# femtoduinoUSB.net
KiCad netlist of a schematic drawn in EAGLE
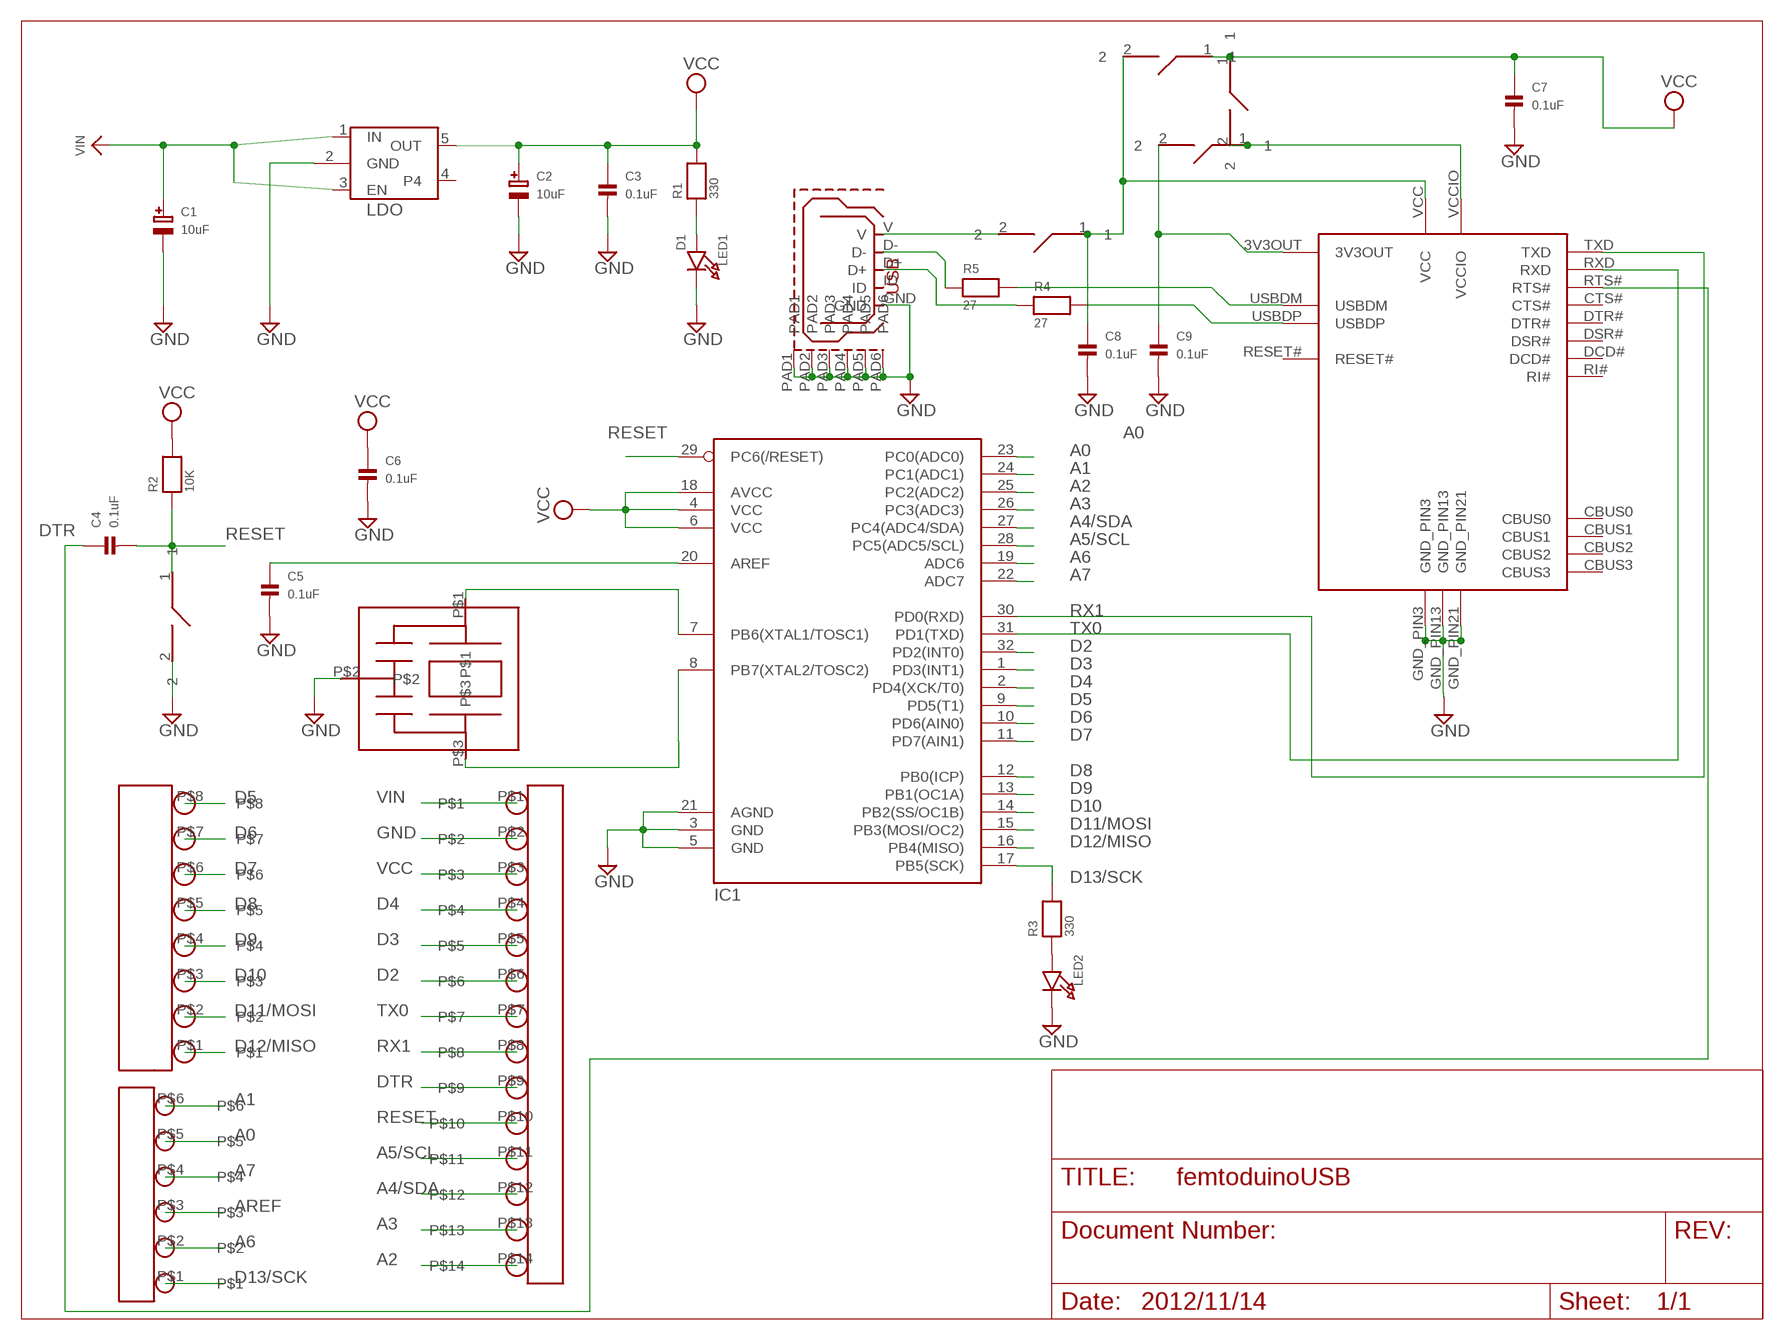
[diagram p0: schematic, sheet 1]

(export (version "E")
  (design (tool "Eeschema 10.0.6"))
  (components
    (comp (ref "C1")
      (value "10uF")
      (footprint "eagle-import:EIA3528-21_B-W")
      (libsource (lib "eagle-import") (part "CAP_TANTALUMB/3528_WAVE"))
    )
    (comp (ref "C2")
      (value "10uF")
      (footprint "eagle-import:EIA3528-21_B-W")
      (libsource (lib "eagle-import") (part "CAP_TANTALUMB/3528_WAVE"))
    )
    (comp (ref "C3")
      (value "0.1uF")
      (footprint "eagle-import:0402")
      (libsource (lib "eagle-import") (part "CAP_CERAMIC0402"))
    )
    (comp (ref "C4")
      (value "0.1uF")
      (footprint "eagle-import:0402")
      (libsource (lib "eagle-import") (part "CAP_CERAMIC0402"))
    )
    (comp (ref "C5")
      (value "0.1uF")
      (footprint "eagle-import:0402")
      (libsource (lib "eagle-import") (part "CAP_CERAMIC0402"))
    )
    (comp (ref "C6")
      (value "0.1uF")
      (footprint "eagle-import:0402")
      (libsource (lib "eagle-import") (part "CAP_CERAMIC0402"))
    )
    (comp (ref "C7")
      (value "0.1uF")
      (footprint "eagle-import:0402")
      (libsource (lib "eagle-import") (part "CAP_CERAMIC0402"))
    )
    (comp (ref "C8")
      (value "0.1uF")
      (footprint "eagle-import:0402")
      (libsource (lib "eagle-import") (part "CAP_CERAMIC0402"))
    )
    (comp (ref "C9")
      (value "0.1uF")
      (footprint "eagle-import:0402")
      (libsource (lib "eagle-import") (part "CAP_CERAMIC0402"))
    )
    (comp (ref "IC1")
      (value "ATMEGA168MLF")
      (footprint "eagle-import:MLF32")
      (libsource (lib "eagle-import") (part "ATMEGA168MLF"))
    )
    (comp (ref "IC2")
      (value "FT231XQ-R")
      (footprint "eagle-import:FTDI_FT231XQ-R_PACKAGE")
      (libsource (lib "eagle-import") (part "FT231XQ-R"))
    )
    (comp (ref "LED1")
      (value "D1")
      (footprint "eagle-import:CHIPLED_0805")
      (libsource (lib "eagle-import") (part "LED0805"))
    )
    (comp (ref "LED2")
      (value "LED0805")
      (footprint "eagle-import:CHIPLED_0805")
      (libsource (lib "eagle-import") (part "LED0805"))
    )
    (comp (ref "R1")
      (value "330")
      (footprint "eagle-import:0402")
      (libsource (lib "eagle-import") (part "RESISTOR0402"))
    )
    (comp (ref "R2")
      (value "10K")
      (footprint "eagle-import:0402")
      (libsource (lib "eagle-import") (part "RESISTOR0402"))
    )
    (comp (ref "R3")
      (value "330")
      (footprint "eagle-import:0402")
      (libsource (lib "eagle-import") (part "RESISTOR0402"))
    )
    (comp (ref "R4")
      (value "27")
      (footprint "eagle-import:0402")
      (libsource (lib "eagle-import") (part "RESISTOR0402"))
    )
    (comp (ref "R5")
      (value "27")
      (footprint "eagle-import:0402")
      (libsource (lib "eagle-import") (part "RESISTOR0402"))
    )
    (comp (ref "SJ1")
      (value "SPST_SMD")
      (footprint "eagle-import:SPST_SMD")
      (libsource (lib "eagle-import") (part "SPST_SMD"))
    )
    (comp (ref "SJ2")
      (value "SPST_SMD")
      (footprint "eagle-import:SPST_SMD")
      (libsource (lib "eagle-import") (part "SPST_SMD"))
    )
    (comp (ref "SJ3")
      (value "SPST_SMD")
      (footprint "eagle-import:SPST_SMD")
      (libsource (lib "eagle-import") (part "SPST_SMD"))
    )
    (comp (ref "SJ4")
      (value "SPST_SMD")
      (footprint "eagle-import:SPST_SMD")
      (libsource (lib "eagle-import") (part "SPST_SMD"))
    )
    (comp (ref "U$2")
      (value "05_PINHEAD_1X6")
      (footprint "eagle-import:05_PINHEAD_1X6_PACKAGE")
      (libsource (lib "eagle-import") (part "05_PINHEAD_1X6"))
    )
    (comp (ref "U$3")
      (value "05_PINHEAD_1X8")
      (footprint "eagle-import:05_PINHEAD_1X8_PACKAGE")
      (libsource (lib "eagle-import") (part "05_PINHEAD_1X8"))
    )
    (comp (ref "U$4")
      (value "05_PINHEAD_1X14")
      (footprint "eagle-import:05_PINHEAD_1X14_PACKAGE")
      (libsource (lib "eagle-import") (part "05_PINHEAD_1X14"))
    )
    (comp (ref "U$5")
      (value "CSTCE16MOV51-RO")
      (footprint "eagle-import:CSTCE16M0V51-RO_PACKAGE")
      (libsource (lib "eagle-import") (part "CSTCE16MOV51-RO"))
    )
    (comp (ref "U$6")
      (value "SPST_SMD")
      (footprint "eagle-import:SPST_SMD")
      (libsource (lib "eagle-import") (part "SPST_SMD"))
    )
    (comp (ref "U1")
      (value "MIC5205")
      (footprint "eagle-import:LDO_REGULATOR")
      (libsource (lib "eagle-import") (part "LDO_REGULATOR"))
    )
    (comp (ref "USB1")
      (value "USB_MICROB")
      (footprint "eagle-import:USB_MICROB_PACKAGE")
      (libsource (lib "eagle-import") (part "USB_MICROB"))
    )
  )
  (nets
    (net (code "1") (name "/A0") (class "Default")
      (node (ref "IC1") (pin "23") (pinfunction "PC0(ADC0)_23") (pintype "bidirectional"))
      (node (ref "U$2") (pin "P$5") (pinfunction "P$5_P$5") (pintype "bidirectional"))
    )
    (net (code "2") (name "/A1") (class "Default")
      (node (ref "IC1") (pin "24") (pinfunction "PC1(ADC1)_24") (pintype "bidirectional"))
      (node (ref "U$2") (pin "P$6") (pinfunction "P$6_P$6") (pintype "bidirectional"))
    )
    (net (code "3") (name "/A2") (class "Default")
      (node (ref "IC1") (pin "25") (pinfunction "PC2(ADC2)_25") (pintype "bidirectional"))
      (node (ref "U$4") (pin "P$14") (pinfunction "P$14_P$14") (pintype "bidirectional"))
    )
    (net (code "4") (name "/A3") (class "Default")
      (node (ref "IC1") (pin "26") (pinfunction "PC3(ADC3)_26") (pintype "bidirectional"))
      (node (ref "U$4") (pin "P$13") (pinfunction "P$13_P$13") (pintype "bidirectional"))
    )
    (net (code "5") (name "/A4{slash}SDA") (class "Default")
      (node (ref "IC1") (pin "27") (pinfunction "PC4(ADC4/SDA)_27") (pintype "bidirectional"))
      (node (ref "U$4") (pin "P$12") (pinfunction "P$12_P$12") (pintype "bidirectional"))
    )
    (net (code "6") (name "/A5{slash}SCL") (class "Default")
      (node (ref "IC1") (pin "28") (pinfunction "PC5(ADC5/SCL)_28") (pintype "bidirectional"))
      (node (ref "U$4") (pin "P$11") (pinfunction "P$11_P$11") (pintype "bidirectional"))
    )
    (net (code "7") (name "/A6") (class "Default")
      (node (ref "IC1") (pin "19") (pinfunction "ADC6_19") (pintype "bidirectional"))
      (node (ref "U$2") (pin "P$2") (pinfunction "P$2_P$2") (pintype "bidirectional"))
    )
    (net (code "8") (name "/A7") (class "Default")
      (node (ref "IC1") (pin "22") (pinfunction "ADC7_22") (pintype "bidirectional"))
      (node (ref "U$2") (pin "P$4") (pinfunction "P$4_P$4") (pintype "bidirectional"))
    )
    (net (code "9") (name "/AREF") (class "Default")
      (node (ref "C5") (pin "1") (pinfunction "P$1_1") (pintype "passive"))
      (node (ref "IC1") (pin "20") (pinfunction "AREF_20") (pintype "bidirectional"))
      (node (ref "U$2") (pin "P$3") (pinfunction "P$3_P$3") (pintype "bidirectional"))
    )
    (net (code "10") (name "/D2") (class "Default")
      (node (ref "IC1") (pin "32") (pinfunction "PD2(INT0)_32") (pintype "bidirectional"))
      (node (ref "U$4") (pin "P$6") (pinfunction "P$6_P$6") (pintype "bidirectional"))
    )
    (net (code "11") (name "/D3") (class "Default")
      (node (ref "IC1") (pin "1") (pinfunction "PD3(INT1)_1") (pintype "bidirectional"))
      (node (ref "U$4") (pin "P$5") (pinfunction "P$5_P$5") (pintype "bidirectional"))
    )
    (net (code "12") (name "/D4") (class "Default")
      (node (ref "IC1") (pin "2") (pinfunction "PD4(XCK/T0)_2") (pintype "bidirectional"))
      (node (ref "U$4") (pin "P$4") (pinfunction "P$4_P$4") (pintype "bidirectional"))
    )
    (net (code "13") (name "/D5") (class "Default")
      (node (ref "IC1") (pin "9") (pinfunction "PD5(T1)_9") (pintype "bidirectional"))
      (node (ref "U$3") (pin "P$8") (pinfunction "P$8_P$8") (pintype "bidirectional"))
    )
    (net (code "14") (name "/D6") (class "Default")
      (node (ref "IC1") (pin "10") (pinfunction "PD6(AIN0)_10") (pintype "bidirectional"))
      (node (ref "U$3") (pin "P$7") (pinfunction "P$7_P$7") (pintype "bidirectional"))
    )
    (net (code "15") (name "/D7") (class "Default")
      (node (ref "IC1") (pin "11") (pinfunction "PD7(AIN1)_11") (pintype "bidirectional"))
      (node (ref "U$3") (pin "P$6") (pinfunction "P$6_P$6") (pintype "bidirectional"))
    )
    (net (code "16") (name "/D8") (class "Default")
      (node (ref "IC1") (pin "12") (pinfunction "PB0(ICP)_12") (pintype "bidirectional"))
      (node (ref "U$3") (pin "P$5") (pinfunction "P$5_P$5") (pintype "bidirectional"))
    )
    (net (code "17") (name "/D9") (class "Default")
      (node (ref "IC1") (pin "13") (pinfunction "PB1(OC1A)_13") (pintype "bidirectional"))
      (node (ref "U$3") (pin "P$4") (pinfunction "P$4_P$4") (pintype "bidirectional"))
    )
    (net (code "18") (name "/D10") (class "Default")
      (node (ref "IC1") (pin "14") (pinfunction "PB2(SS/OC1B)_14") (pintype "bidirectional"))
      (node (ref "U$3") (pin "P$3") (pinfunction "P$3_P$3") (pintype "bidirectional"))
    )
    (net (code "19") (name "/D11{slash}MOSI") (class "Default")
      (node (ref "IC1") (pin "15") (pinfunction "PB3(MOSI/OC2)_15") (pintype "bidirectional"))
      (node (ref "U$3") (pin "P$2") (pinfunction "P$2_P$2") (pintype "bidirectional"))
    )
    (net (code "20") (name "/D12{slash}MISO") (class "Default")
      (node (ref "IC1") (pin "16") (pinfunction "PB4(MISO)_16") (pintype "bidirectional"))
      (node (ref "U$3") (pin "P$1") (pinfunction "P$1_P$1") (pintype "bidirectional"))
    )
    (net (code "21") (name "/D13{slash}SCK") (class "Default")
      (node (ref "IC1") (pin "17") (pinfunction "PB5(SCK)_17") (pintype "bidirectional"))
      (node (ref "R3") (pin "2") (pinfunction "2_2") (pintype "passive"))
      (node (ref "U$2") (pin "P$1") (pinfunction "P$1_P$1") (pintype "bidirectional"))
    )
    (net (code "22") (name "/DTR") (class "Default")
      (node (ref "C4") (pin "1") (pinfunction "P$1_1") (pintype "passive"))
      (node (ref "IC2") (pin "RTS#") (pinfunction "RTS#_RTS#") (pintype "bidirectional"))
      (node (ref "U$4") (pin "P$9") (pinfunction "P$9_P$9") (pintype "bidirectional"))
    )
    (net (code "23") (name "/RESET") (class "Default")
      (node (ref "C4") (pin "2") (pinfunction "P$2_2") (pintype "passive"))
      (node (ref "IC1") (pin "29") (pinfunction "PC6(/RESET)_29") (pintype "bidirectional"))
      (node (ref "R2") (pin "1") (pinfunction "1_1") (pintype "passive"))
      (node (ref "U$4") (pin "P$10") (pinfunction "P$10_P$10") (pintype "bidirectional"))
      (node (ref "U$6") (pin "1") (pinfunction "1_1") (pintype "bidirectional"))
    )
    (net (code "24") (name "/RX1") (class "Default")
      (node (ref "IC1") (pin "30") (pinfunction "PD0(RXD)_30") (pintype "bidirectional"))
      (node (ref "IC2") (pin "TXD") (pinfunction "TXD_TXD") (pintype "bidirectional"))
      (node (ref "U$4") (pin "P$8") (pinfunction "P$8_P$8") (pintype "bidirectional"))
    )
    (net (code "25") (name "/TX0") (class "Default")
      (node (ref "IC1") (pin "31") (pinfunction "PD1(TXD)_31") (pintype "bidirectional"))
      (node (ref "IC2") (pin "RXD") (pinfunction "RXD_RXD") (pintype "bidirectional"))
      (node (ref "U$4") (pin "P$7") (pinfunction "P$7_P$7") (pintype "bidirectional"))
    )
    (net (code "26") (name "GND") (class "Default")
      (node (ref "C1") (pin "-") (pinfunction "-_-") (pintype "passive"))
      (node (ref "C2") (pin "-") (pinfunction "-_-") (pintype "passive"))
      (node (ref "C3") (pin "2") (pinfunction "P$2_2") (pintype "passive"))
      (node (ref "C5") (pin "2") (pinfunction "P$2_2") (pintype "passive"))
      (node (ref "C6") (pin "2") (pinfunction "P$2_2") (pintype "passive"))
      (node (ref "C7") (pin "2") (pinfunction "P$2_2") (pintype "passive"))
      (node (ref "C8") (pin "2") (pinfunction "P$2_2") (pintype "passive"))
      (node (ref "C9") (pin "2") (pinfunction "P$2_2") (pintype "passive"))
      (node (ref "IC1") (pin "21") (pinfunction "AGND_21") (pintype "bidirectional"))
      (node (ref "IC1") (pin "3") (pinfunction "GND_3") (pintype "bidirectional"))
      (node (ref "IC1") (pin "5") (pinfunction "GND_5") (pintype "bidirectional"))
      (node (ref "IC2") (pin "GND_PIN13") (pinfunction "GND_PIN13_GND_PIN13") (pintype "bidirectional"))
      (node (ref "IC2") (pin "GND_PIN21") (pinfunction "GND_PIN21_GND_PIN21") (pintype "bidirectional"))
      (node (ref "IC2") (pin "GND_PIN3") (pinfunction "GND_PIN3_GND_PIN3") (pintype "bidirectional"))
      (node (ref "LED1") (pin "C") (pinfunction "C_C") (pintype "passive"))
      (node (ref "LED2") (pin "C") (pinfunction "C_C") (pintype "passive"))
      (node (ref "U$4") (pin "P$2") (pinfunction "P$2_P$2") (pintype "bidirectional"))
      (node (ref "U$5") (pin "P$2") (pinfunction "P$2_P$2") (pintype "bidirectional"))
      (node (ref "U$6") (pin "2") (pinfunction "2_2") (pintype "bidirectional"))
      (node (ref "U1") (pin "2") (pinfunction "GND_2") (pintype "bidirectional"))
      (node (ref "USB1") (pin "GND") (pinfunction "GND_GND") (pintype "bidirectional"))
      (node (ref "USB1") (pin "PAD1") (pinfunction "PAD1_PAD1") (pintype "bidirectional"))
      (node (ref "USB1") (pin "PAD2") (pinfunction "PAD2_PAD2") (pintype "bidirectional"))
      (node (ref "USB1") (pin "PAD3") (pinfunction "PAD3_PAD3") (pintype "bidirectional"))
      (node (ref "USB1") (pin "PAD4") (pinfunction "PAD4_PAD4") (pintype "bidirectional"))
      (node (ref "USB1") (pin "PAD5") (pinfunction "PAD5_PAD5") (pintype "bidirectional"))
      (node (ref "USB1") (pin "PAD6") (pinfunction "PAD6_PAD6") (pintype "bidirectional"))
    )
    (net (code "27") (name "Net-(C8-P$1)") (class "Default")
      (node (ref "C8") (pin "1") (pinfunction "P$1_1") (pintype "passive"))
      (node (ref "IC2") (pin "VCC") (pinfunction "VCC_VCC") (pintype "bidirectional"))
      (node (ref "SJ1") (pin "1") (pinfunction "1_1") (pintype "bidirectional"))
      (node (ref "SJ2") (pin "2") (pinfunction "2_2") (pintype "bidirectional"))
    )
    (net (code "28") (name "Net-(C9-P$1)") (class "Default")
      (node (ref "C9") (pin "1") (pinfunction "P$1_1") (pintype "passive"))
      (node (ref "IC2") (pin "3V3OUT") (pinfunction "3V3OUT_3V3OUT") (pintype "bidirectional"))
      (node (ref "SJ4") (pin "2") (pinfunction "2_2") (pintype "bidirectional"))
    )
    (net (code "29") (name "Net-(IC1-PB6(XTAL1{slash}TOSC1))") (class "Default")
      (node (ref "IC1") (pin "7") (pinfunction "PB6(XTAL1/TOSC1)_7") (pintype "bidirectional"))
      (node (ref "U$5") (pin "P$1") (pinfunction "P$1_P$1") (pintype "bidirectional"))
    )
    (net (code "30") (name "Net-(IC1-PB7(XTAL2{slash}TOSC2))") (class "Default")
      (node (ref "IC1") (pin "8") (pinfunction "PB7(XTAL2/TOSC2)_8") (pintype "bidirectional"))
      (node (ref "U$5") (pin "P$3") (pinfunction "P$3_P$3") (pintype "bidirectional"))
    )
    (net (code "31") (name "Net-(IC2-PadUSBDM)") (class "Default")
      (node (ref "IC2") (pin "USBDM") (pinfunction "USBDM_USBDM") (pintype "bidirectional"))
      (node (ref "R5") (pin "2") (pinfunction "2_2") (pintype "passive"))
    )
    (net (code "32") (name "Net-(IC2-PadUSBDP)") (class "Default")
      (node (ref "IC2") (pin "USBDP") (pinfunction "USBDP_USBDP") (pintype "bidirectional"))
      (node (ref "R4") (pin "2") (pinfunction "2_2") (pintype "passive"))
    )
    (net (code "33") (name "Net-(IC2-PadVCCIO)") (class "Default")
      (node (ref "IC2") (pin "VCCIO") (pinfunction "VCCIO_VCCIO") (pintype "bidirectional"))
      (node (ref "SJ3") (pin "2") (pinfunction "2_2") (pintype "bidirectional"))
      (node (ref "SJ4") (pin "1") (pinfunction "1_1") (pintype "bidirectional"))
    )
    (net (code "34") (name "Net-(LED1-PadA)") (class "Default")
      (node (ref "LED1") (pin "A") (pinfunction "A_A") (pintype "passive"))
      (node (ref "R1") (pin "1") (pinfunction "1_1") (pintype "passive"))
    )
    (net (code "35") (name "Net-(LED2-PadA)") (class "Default")
      (node (ref "LED2") (pin "A") (pinfunction "A_A") (pintype "passive"))
      (node (ref "R3") (pin "1") (pinfunction "1_1") (pintype "passive"))
    )
    (net (code "36") (name "Net-(R4-Pad1)") (class "Default")
      (node (ref "R4") (pin "1") (pinfunction "1_1") (pintype "passive"))
      (node (ref "USB1") (pin "D+") (pinfunction "D+_D+") (pintype "bidirectional"))
    )
    (net (code "37") (name "Net-(R5-Pad1)") (class "Default")
      (node (ref "R5") (pin "1") (pinfunction "1_1") (pintype "passive"))
      (node (ref "USB1") (pin "D-") (pinfunction "D-_D-") (pintype "bidirectional"))
    )
    (net (code "38") (name "VCC") (class "Default")
      (node (ref "C2") (pin "+") (pinfunction "+_+") (pintype "passive"))
      (node (ref "C3") (pin "1") (pinfunction "P$1_1") (pintype "passive"))
      (node (ref "C6") (pin "1") (pinfunction "P$1_1") (pintype "passive"))
      (node (ref "C7") (pin "1") (pinfunction "P$1_1") (pintype "passive"))
      (node (ref "IC1") (pin "18") (pinfunction "AVCC_18") (pintype "bidirectional"))
      (node (ref "IC1") (pin "4") (pinfunction "VCC_4") (pintype "bidirectional"))
      (node (ref "IC1") (pin "6") (pinfunction "VCC_6") (pintype "bidirectional"))
      (node (ref "R1") (pin "2") (pinfunction "2_2") (pintype "passive"))
      (node (ref "R2") (pin "2") (pinfunction "2_2") (pintype "passive"))
      (node (ref "SJ1") (pin "2") (pinfunction "2_2") (pintype "bidirectional"))
      (node (ref "SJ2") (pin "1") (pinfunction "1_1") (pintype "bidirectional"))
      (node (ref "SJ3") (pin "1") (pinfunction "1_1") (pintype "bidirectional"))
      (node (ref "U$4") (pin "P$3") (pinfunction "P$3_P$3") (pintype "bidirectional"))
      (node (ref "U1") (pin "5") (pinfunction "OUT_5") (pintype "bidirectional"))
      (node (ref "USB1") (pin "V") (pinfunction "V_V") (pintype "bidirectional"))
    )
    (net (code "39") (name "VIN") (class "Default")
      (node (ref "C1") (pin "+") (pinfunction "+_+") (pintype "passive"))
      (node (ref "U$4") (pin "P$1") (pinfunction "P$1_P$1") (pintype "bidirectional"))
      (node (ref "U1") (pin "1") (pinfunction "IN_1") (pintype "bidirectional"))
      (node (ref "U1") (pin "3") (pinfunction "EN_3") (pintype "bidirectional"))
    )
    (net (code "40") (name "unconnected-(IC2-PadCBUS0)") (class "Default")
      (node (ref "IC2") (pin "CBUS0") (pinfunction "CBUS0_CBUS0") (pintype "bidirectional"))
    )
    (net (code "41") (name "unconnected-(IC2-PadCBUS1)") (class "Default")
      (node (ref "IC2") (pin "CBUS1") (pinfunction "CBUS1_CBUS1") (pintype "bidirectional"))
    )
    (net (code "42") (name "unconnected-(IC2-PadCBUS2)") (class "Default")
      (node (ref "IC2") (pin "CBUS2") (pinfunction "CBUS2_CBUS2") (pintype "bidirectional"))
    )
    (net (code "43") (name "unconnected-(IC2-PadCBUS3)") (class "Default")
      (node (ref "IC2") (pin "CBUS3") (pinfunction "CBUS3_CBUS3") (pintype "bidirectional"))
    )
    (net (code "44") (name "unconnected-(IC2-PadCTS#)") (class "Default")
      (node (ref "IC2") (pin "CTS#") (pinfunction "CTS#_CTS#") (pintype "bidirectional"))
    )
    (net (code "45") (name "unconnected-(IC2-PadDCD#)") (class "Default")
      (node (ref "IC2") (pin "DCD#") (pinfunction "DCD#_DCD#") (pintype "bidirectional"))
    )
    (net (code "46") (name "unconnected-(IC2-PadDSR#)") (class "Default")
      (node (ref "IC2") (pin "DSR#") (pinfunction "DSR#_DSR#") (pintype "bidirectional"))
    )
    (net (code "47") (name "unconnected-(IC2-PadDTR#)") (class "Default")
      (node (ref "IC2") (pin "DTR#") (pinfunction "DTR#_DTR#") (pintype "bidirectional"))
    )
    (net (code "48") (name "unconnected-(IC2-PadRESET#)") (class "Default")
      (node (ref "IC2") (pin "RESET#") (pinfunction "RESET#_RESET#") (pintype "bidirectional"))
    )
    (net (code "49") (name "unconnected-(IC2-PadRI#)") (class "Default")
      (node (ref "IC2") (pin "RI#") (pinfunction "RI#_RI#") (pintype "bidirectional"))
    )
    (net (code "50") (name "unconnected-(U1-P4-Pad4)") (class "Default")
      (node (ref "U1") (pin "4") (pinfunction "P4_4") (pintype "bidirectional"))
    )
    (net (code "51") (name "unconnected-(USB1-PadID)") (class "Default")
      (node (ref "USB1") (pin "ID") (pinfunction "ID_ID") (pintype "bidirectional"))
    )
  )
)
